# INTERFACE_PWR_LS_HS.net
KiCad netlist of a schematic drawn in Altium Designer
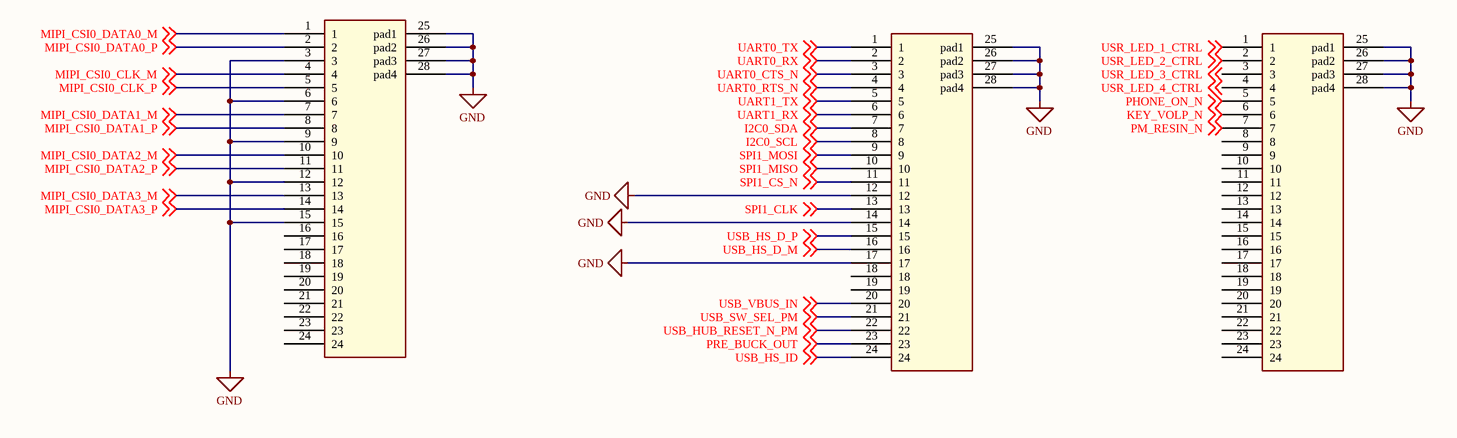
[diagram p0: INTERFACE_PWR_LS_HS.SchDoc]

(export (version "E")
  (design (tool "Eeschema 10.0.6"))
  (components
    (comp (ref "CN0")
      (value "CON24_0")
      (footprint "c0402")
      (libsource (lib "MSM8916_DRAM_PMIC_REF_Library") (part "CON24_0"))
    )
    (comp (ref "CN1")
      (value "CON24_0")
      (footprint "c0402")
      (libsource (lib "MSM8916_DRAM_PMIC_REF_Library") (part "CON24_0"))
    )
    (comp (ref "CN2")
      (value "CON24_0")
      (footprint "c0402")
      (libsource (lib "MSM8916_DRAM_PMIC_REF_Library") (part "CON24_0"))
    )
  )
  (nets
    (net (code "1") (name "GND") (class "Default")
      (node (ref "CN0") (pin "12") (pinfunction "12_12") (pintype "passive"))
      (node (ref "CN0") (pin "15") (pinfunction "15_15") (pintype "passive"))
      (node (ref "CN0") (pin "25") (pinfunction "pad1_25") (pintype "passive"))
      (node (ref "CN0") (pin "26") (pinfunction "pad2_26") (pintype "passive"))
      (node (ref "CN0") (pin "27") (pinfunction "pad3_27") (pintype "passive"))
      (node (ref "CN0") (pin "28") (pinfunction "pad4_28") (pintype "passive"))
      (node (ref "CN0") (pin "3") (pinfunction "3_3") (pintype "passive"))
      (node (ref "CN0") (pin "6") (pinfunction "6_6") (pintype "passive"))
      (node (ref "CN0") (pin "9") (pinfunction "9_9") (pintype "passive"))
      (node (ref "CN1") (pin "12") (pinfunction "12_12") (pintype "passive"))
      (node (ref "CN1") (pin "14") (pinfunction "14_14") (pintype "passive"))
      (node (ref "CN1") (pin "17") (pinfunction "17_17") (pintype "passive"))
      (node (ref "CN1") (pin "25") (pinfunction "pad1_25") (pintype "passive"))
      (node (ref "CN1") (pin "26") (pinfunction "pad2_26") (pintype "passive"))
      (node (ref "CN1") (pin "27") (pinfunction "pad3_27") (pintype "passive"))
      (node (ref "CN1") (pin "28") (pinfunction "pad4_28") (pintype "passive"))
      (node (ref "CN2") (pin "25") (pinfunction "pad1_25") (pintype "passive"))
      (node (ref "CN2") (pin "26") (pinfunction "pad2_26") (pintype "passive"))
      (node (ref "CN2") (pin "27") (pinfunction "pad3_27") (pintype "passive"))
      (node (ref "CN2") (pin "28") (pinfunction "pad4_28") (pintype "passive"))
    )
    (net (code "2") (name "I2C0_SCL") (class "Default")
      (node (ref "CN1") (pin "8") (pinfunction "8_8") (pintype "passive"))
    )
    (net (code "3") (name "I2C0_SDA") (class "Default")
      (node (ref "CN1") (pin "7") (pinfunction "7_7") (pintype "passive"))
    )
    (net (code "4") (name "KEY_VOLP_N") (class "Default")
      (node (ref "CN2") (pin "6") (pinfunction "6_6") (pintype "passive"))
    )
    (net (code "5") (name "MIPI_CSI0_CLK_M") (class "Default")
      (node (ref "CN0") (pin "4") (pinfunction "4_4") (pintype "passive"))
    )
    (net (code "6") (name "MIPI_CSI0_CLK_P") (class "Default")
      (node (ref "CN0") (pin "5") (pinfunction "5_5") (pintype "passive"))
    )
    (net (code "7") (name "MIPI_CSI0_DATA0_M") (class "Default")
      (node (ref "CN0") (pin "1") (pinfunction "1_1") (pintype "passive"))
    )
    (net (code "8") (name "MIPI_CSI0_DATA0_P") (class "Default")
      (node (ref "CN0") (pin "2") (pinfunction "2_2") (pintype "passive"))
    )
    (net (code "9") (name "MIPI_CSI0_DATA1_M") (class "Default")
      (node (ref "CN0") (pin "7") (pinfunction "7_7") (pintype "passive"))
    )
    (net (code "10") (name "MIPI_CSI0_DATA1_P") (class "Default")
      (node (ref "CN0") (pin "8") (pinfunction "8_8") (pintype "passive"))
    )
    (net (code "11") (name "MIPI_CSI0_DATA2_M") (class "Default")
      (node (ref "CN0") (pin "10") (pinfunction "10_10") (pintype "passive"))
    )
    (net (code "12") (name "MIPI_CSI0_DATA2_P") (class "Default")
      (node (ref "CN0") (pin "11") (pinfunction "11_11") (pintype "passive"))
    )
    (net (code "13") (name "MIPI_CSI0_DATA3_M") (class "Default")
      (node (ref "CN0") (pin "13") (pinfunction "13_13") (pintype "passive"))
    )
    (net (code "14") (name "MIPI_CSI0_DATA3_P") (class "Default")
      (node (ref "CN0") (pin "14") (pinfunction "14_14") (pintype "passive"))
    )
    (net (code "15") (name "PHONE_ON_N") (class "Default")
      (node (ref "CN2") (pin "5") (pinfunction "5_5") (pintype "passive"))
    )
    (net (code "16") (name "PM_RESIN_N") (class "Default")
      (node (ref "CN2") (pin "7") (pinfunction "7_7") (pintype "passive"))
    )
    (net (code "17") (name "PRE_BUCK_OUT") (class "Default")
      (node (ref "CN1") (pin "23") (pinfunction "23_23") (pintype "passive"))
    )
    (net (code "18") (name "SPI1_CLK") (class "Default")
      (node (ref "CN1") (pin "13") (pinfunction "13_13") (pintype "passive"))
    )
    (net (code "19") (name "SPI1_CS_N") (class "Default")
      (node (ref "CN1") (pin "11") (pinfunction "11_11") (pintype "passive"))
    )
    (net (code "20") (name "SPI1_MISO") (class "Default")
      (node (ref "CN1") (pin "10") (pinfunction "10_10") (pintype "passive"))
    )
    (net (code "21") (name "SPI1_MOSI") (class "Default")
      (node (ref "CN1") (pin "9") (pinfunction "9_9") (pintype "passive"))
    )
    (net (code "22") (name "UART0_CTS_N") (class "Default")
      (node (ref "CN1") (pin "3") (pinfunction "3_3") (pintype "passive"))
    )
    (net (code "23") (name "UART0_RTS_N") (class "Default")
      (node (ref "CN1") (pin "4") (pinfunction "4_4") (pintype "passive"))
    )
    (net (code "24") (name "UART0_RX") (class "Default")
      (node (ref "CN1") (pin "2") (pinfunction "2_2") (pintype "passive"))
    )
    (net (code "25") (name "UART0_TX") (class "Default")
      (node (ref "CN1") (pin "1") (pinfunction "1_1") (pintype "passive"))
    )
    (net (code "26") (name "UART1_RX") (class "Default")
      (node (ref "CN1") (pin "6") (pinfunction "6_6") (pintype "passive"))
    )
    (net (code "27") (name "UART1_TX") (class "Default")
      (node (ref "CN1") (pin "5") (pinfunction "5_5") (pintype "passive"))
    )
    (net (code "28") (name "USB_HS_D_M") (class "Default")
      (node (ref "CN1") (pin "16") (pinfunction "16_16") (pintype "passive"))
    )
    (net (code "29") (name "USB_HS_D_P") (class "Default")
      (node (ref "CN1") (pin "15") (pinfunction "15_15") (pintype "passive"))
    )
    (net (code "30") (name "USB_HS_ID") (class "Default")
      (node (ref "CN1") (pin "24") (pinfunction "24_24") (pintype "passive"))
    )
    (net (code "31") (name "USB_HUB_RESET_N_PM") (class "Default")
      (node (ref "CN1") (pin "22") (pinfunction "22_22") (pintype "passive"))
    )
    (net (code "32") (name "USB_SW_SEL_PM") (class "Default")
      (node (ref "CN1") (pin "21") (pinfunction "21_21") (pintype "passive"))
    )
    (net (code "33") (name "USB_VBUS_IN") (class "Default")
      (node (ref "CN1") (pin "20") (pinfunction "20_20") (pintype "passive"))
    )
    (net (code "34") (name "USR_LED_1_CTRL") (class "Default")
      (node (ref "CN2") (pin "1") (pinfunction "1_1") (pintype "passive"))
    )
    (net (code "35") (name "USR_LED_2_CTRL") (class "Default")
      (node (ref "CN2") (pin "2") (pinfunction "2_2") (pintype "passive"))
    )
    (net (code "36") (name "USR_LED_3_CTRL") (class "Default")
      (node (ref "CN2") (pin "3") (pinfunction "3_3") (pintype "passive"))
    )
    (net (code "37") (name "USR_LED_4_CTRL") (class "Default")
      (node (ref "CN2") (pin "4") (pinfunction "4_4") (pintype "passive"))
    )
    (net (code "38") (name "unconnected-(CN0-Pad16)") (class "Default")
      (node (ref "CN0") (pin "16") (pinfunction "16_16") (pintype "passive"))
    )
    (net (code "39") (name "unconnected-(CN0-Pad17)") (class "Default")
      (node (ref "CN0") (pin "17") (pinfunction "17_17") (pintype "passive"))
    )
    (net (code "40") (name "unconnected-(CN0-Pad18)") (class "Default")
      (node (ref "CN0") (pin "18") (pinfunction "18_18") (pintype "passive"))
    )
    (net (code "41") (name "unconnected-(CN0-Pad19)") (class "Default")
      (node (ref "CN0") (pin "19") (pinfunction "19_19") (pintype "passive"))
    )
    (net (code "42") (name "unconnected-(CN0-Pad20)") (class "Default")
      (node (ref "CN0") (pin "20") (pinfunction "20_20") (pintype "passive"))
    )
    (net (code "43") (name "unconnected-(CN0-Pad21)") (class "Default")
      (node (ref "CN0") (pin "21") (pinfunction "21_21") (pintype "passive"))
    )
    (net (code "44") (name "unconnected-(CN0-Pad22)") (class "Default")
      (node (ref "CN0") (pin "22") (pinfunction "22_22") (pintype "passive"))
    )
    (net (code "45") (name "unconnected-(CN0-Pad23)") (class "Default")
      (node (ref "CN0") (pin "23") (pinfunction "23_23") (pintype "passive"))
    )
    (net (code "46") (name "unconnected-(CN0-Pad24)") (class "Default")
      (node (ref "CN0") (pin "24") (pinfunction "24_24") (pintype "passive"))
    )
    (net (code "47") (name "unconnected-(CN1-Pad18)") (class "Default")
      (node (ref "CN1") (pin "18") (pinfunction "18_18") (pintype "passive"))
    )
    (net (code "48") (name "unconnected-(CN1-Pad19)") (class "Default")
      (node (ref "CN1") (pin "19") (pinfunction "19_19") (pintype "passive"))
    )
    (net (code "49") (name "unconnected-(CN2-Pad8)") (class "Default")
      (node (ref "CN2") (pin "8") (pinfunction "8_8") (pintype "passive"))
    )
    (net (code "50") (name "unconnected-(CN2-Pad9)") (class "Default")
      (node (ref "CN2") (pin "9") (pinfunction "9_9") (pintype "passive"))
    )
    (net (code "51") (name "unconnected-(CN2-Pad10)") (class "Default")
      (node (ref "CN2") (pin "10") (pinfunction "10_10") (pintype "passive"))
    )
    (net (code "52") (name "unconnected-(CN2-Pad11)") (class "Default")
      (node (ref "CN2") (pin "11") (pinfunction "11_11") (pintype "passive"))
    )
    (net (code "53") (name "unconnected-(CN2-Pad12)") (class "Default")
      (node (ref "CN2") (pin "12") (pinfunction "12_12") (pintype "passive"))
    )
    (net (code "54") (name "unconnected-(CN2-Pad13)") (class "Default")
      (node (ref "CN2") (pin "13") (pinfunction "13_13") (pintype "passive"))
    )
    (net (code "55") (name "unconnected-(CN2-Pad14)") (class "Default")
      (node (ref "CN2") (pin "14") (pinfunction "14_14") (pintype "passive"))
    )
    (net (code "56") (name "unconnected-(CN2-Pad15)") (class "Default")
      (node (ref "CN2") (pin "15") (pinfunction "15_15") (pintype "passive"))
    )
    (net (code "57") (name "unconnected-(CN2-Pad16)") (class "Default")
      (node (ref "CN2") (pin "16") (pinfunction "16_16") (pintype "passive"))
    )
    (net (code "58") (name "unconnected-(CN2-Pad17)") (class "Default")
      (node (ref "CN2") (pin "17") (pinfunction "17_17") (pintype "passive"))
    )
    (net (code "59") (name "unconnected-(CN2-Pad18)") (class "Default")
      (node (ref "CN2") (pin "18") (pinfunction "18_18") (pintype "passive"))
    )
    (net (code "60") (name "unconnected-(CN2-Pad19)") (class "Default")
      (node (ref "CN2") (pin "19") (pinfunction "19_19") (pintype "passive"))
    )
    (net (code "61") (name "unconnected-(CN2-Pad20)") (class "Default")
      (node (ref "CN2") (pin "20") (pinfunction "20_20") (pintype "passive"))
    )
    (net (code "62") (name "unconnected-(CN2-Pad21)") (class "Default")
      (node (ref "CN2") (pin "21") (pinfunction "21_21") (pintype "passive"))
    )
    (net (code "63") (name "unconnected-(CN2-Pad22)") (class "Default")
      (node (ref "CN2") (pin "22") (pinfunction "22_22") (pintype "passive"))
    )
    (net (code "64") (name "unconnected-(CN2-Pad23)") (class "Default")
      (node (ref "CN2") (pin "23") (pinfunction "23_23") (pintype "passive"))
    )
    (net (code "65") (name "unconnected-(CN2-Pad24)") (class "Default")
      (node (ref "CN2") (pin "24") (pinfunction "24_24") (pintype "passive"))
    )
  )
)
